# 1_Power_Supply.net
KiCad netlist of a schematic drawn in Altium Designer
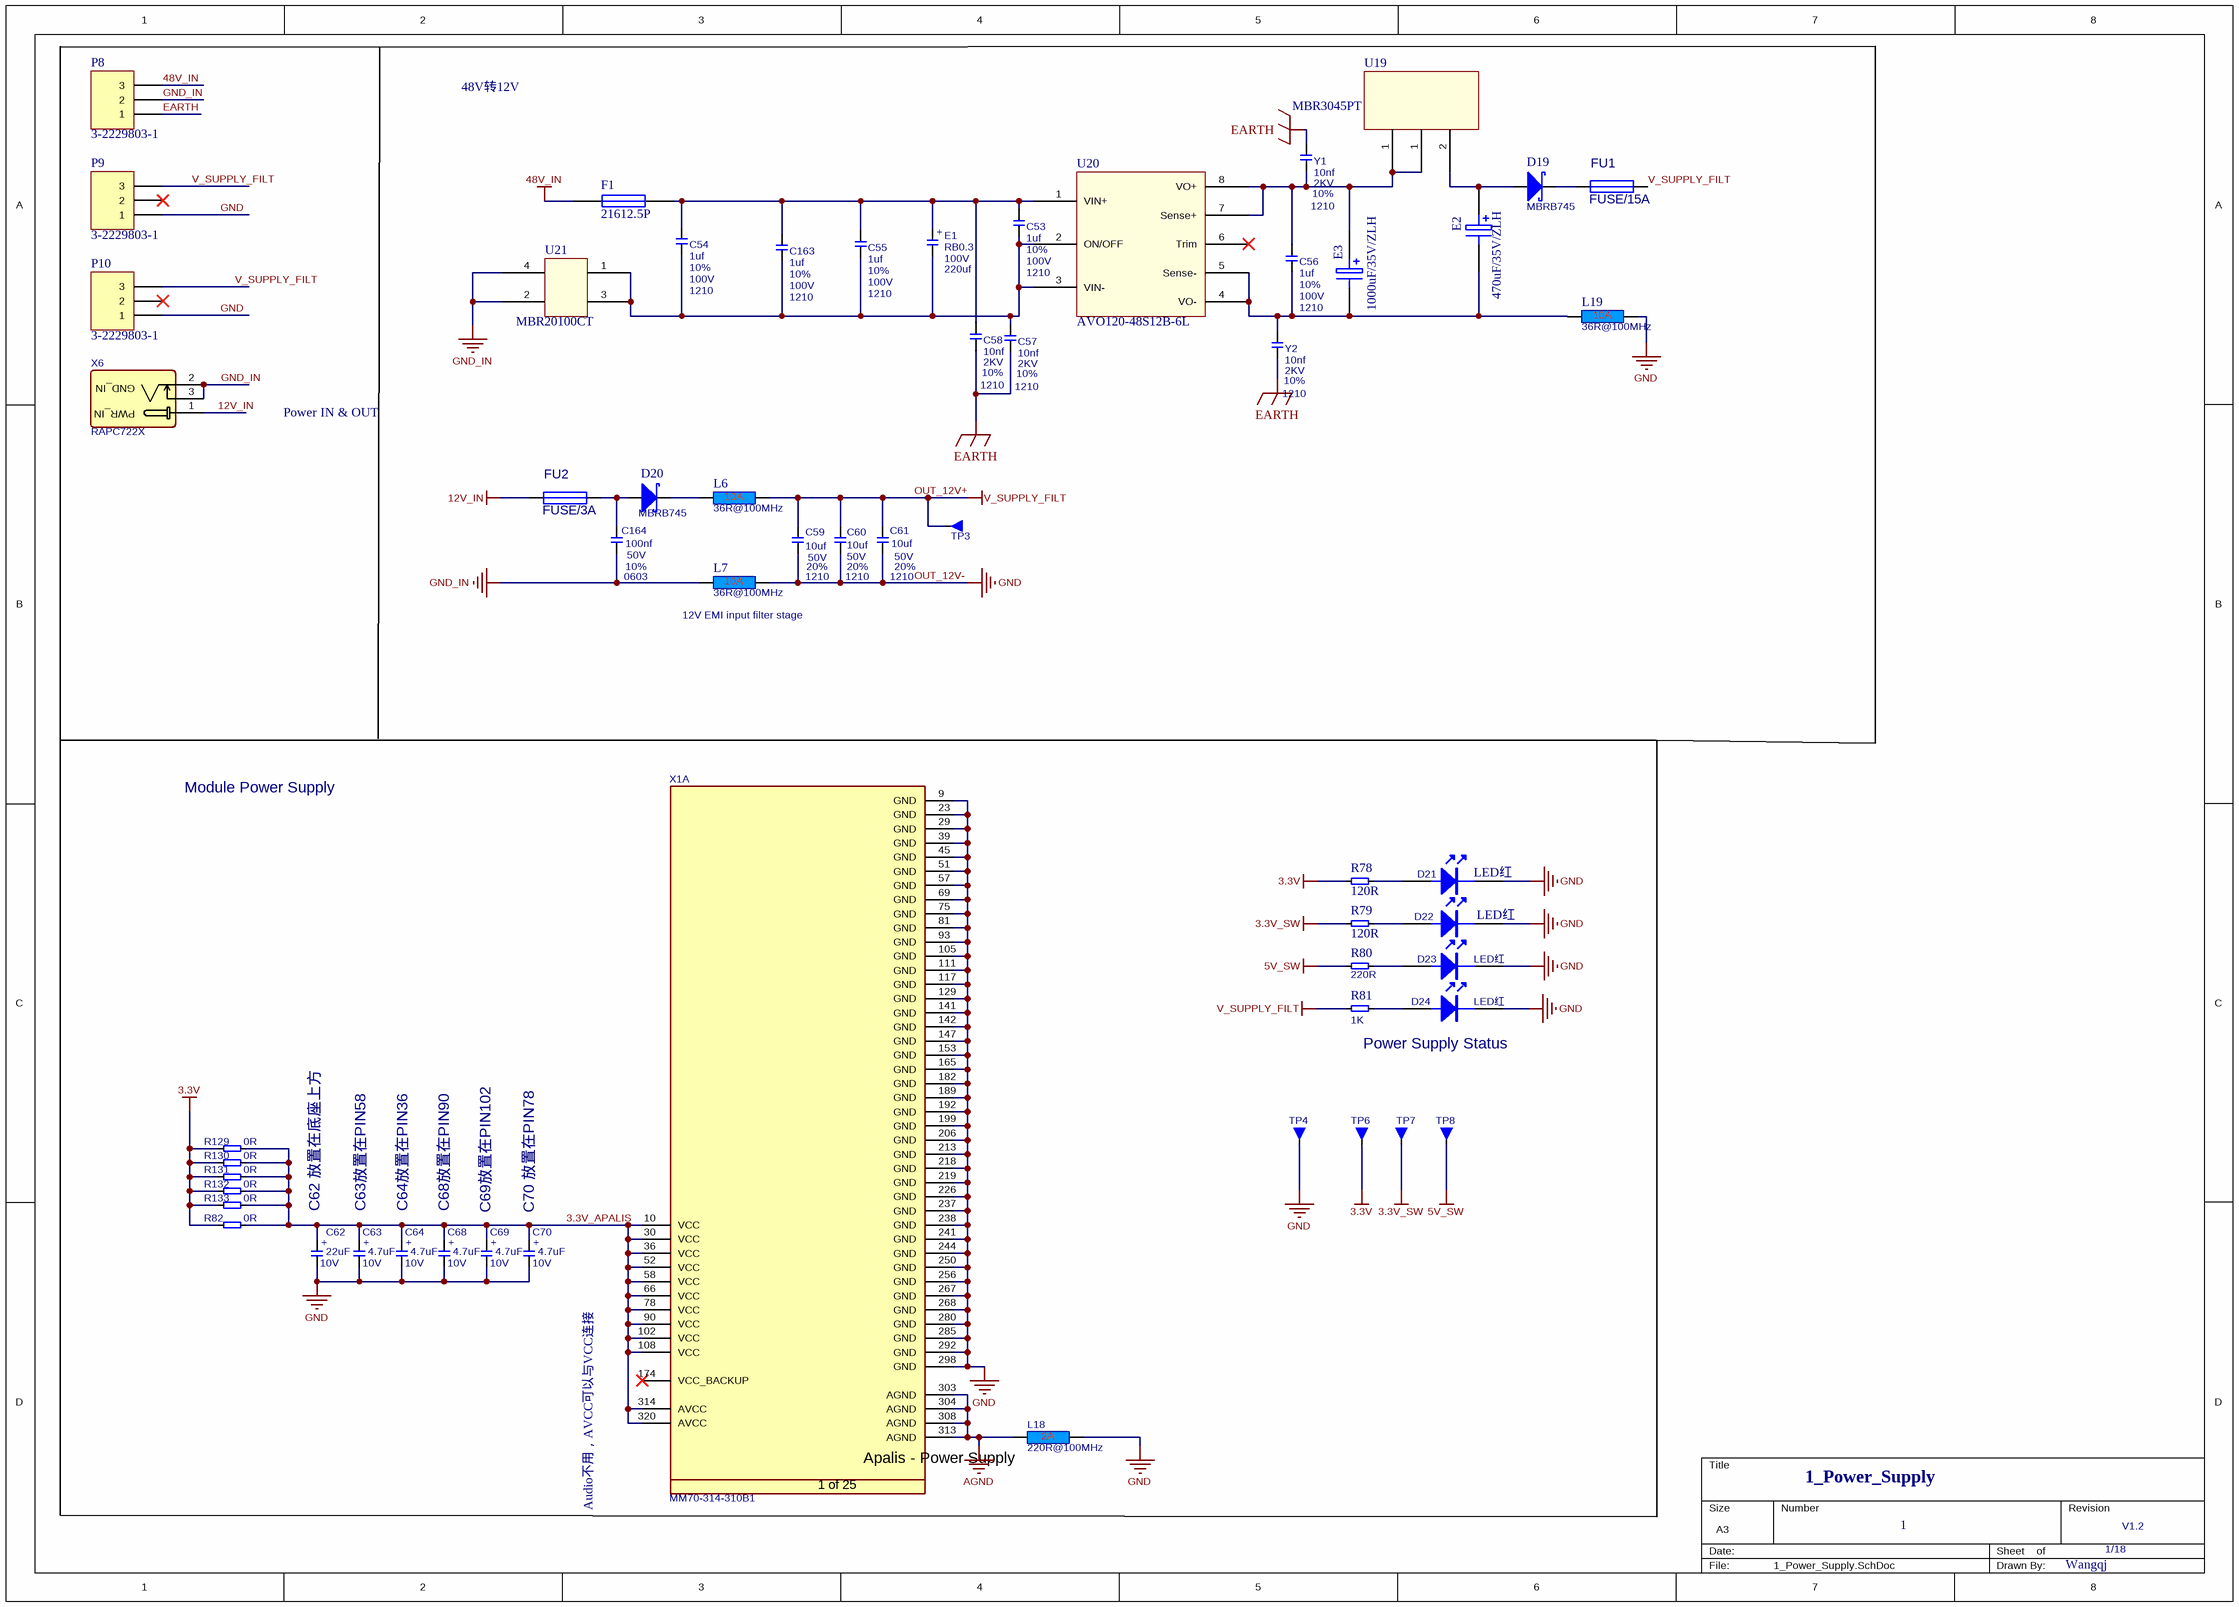
[diagram p0: 1_Power_Supply.SchDoc]

(export (version "E")
  (design (tool "Eeschema 10.0.6"))
  (components
    (comp (ref "C53")
      (value "1uf")
      (footprint "1210")
      (description "33pf-50V-5%-0603")
      (fields
        (field (name "TOLERANCE") "10%")
        (field (name "RATING") "100V")
        (field (name "Comment") "1uf-100V-10%-1210")
      )
      (libsource (lib "WangQJ") (part "C-Ceramic"))
    )
    (comp (ref "C54")
      (value "1uf")
      (footprint "1210")
      (description "33pf-50V-5%-0603")
      (fields
        (field (name "TOLERANCE") "10%")
        (field (name "RATING") "100V")
        (field (name "Comment") "1uf-100V-10%-1210")
      )
      (libsource (lib "WangQJ") (part "C-Ceramic"))
    )
    (comp (ref "C55")
      (value "1uf")
      (footprint "1210")
      (description "33pf-50V-5%-0603")
      (fields
        (field (name "TOLERANCE") "10%")
        (field (name "RATING") "100V")
        (field (name "Comment") "1uf-100V-10%-1210")
      )
      (libsource (lib "WangQJ") (part "C-Ceramic"))
    )
    (comp (ref "C56")
      (value "1uf")
      (footprint "1210")
      (description "33pf-50V-5%-0603")
      (fields
        (field (name "TOLERANCE") "10%")
        (field (name "RATING") "100V")
        (field (name "Comment") "1uf-100V-10%-1210")
      )
      (libsource (lib "WangQJ") (part "C-Ceramic"))
    )
    (comp (ref "C57")
      (value "10nf")
      (footprint "1210")
      (description "33pf-50V-5%-0603")
      (fields
        (field (name "TOLERANCE") "10%")
        (field (name "RATING") "2KV")
        (field (name "Comment") "10nf-2KV-10%-1210")
      )
      (libsource (lib "WangQJ") (part "C-Ceramic"))
    )
    (comp (ref "C58")
      (value "10nf")
      (footprint "1210")
      (description "33pf-50V-5%-0603")
      (fields
        (field (name "TOLERANCE") "10%")
        (field (name "RATING") "2KV")
        (field (name "Comment") "10nf-2KV-10%-1210")
      )
      (libsource (lib "WangQJ") (part "C-Ceramic"))
    )
    (comp (ref "C59")
      (value "10uf")
      (footprint "1210")
      (description "Capacitor Ceramic X5R 10uF 50V 20% 1210")
      (fields
        (field (name "TOLERANCE") "20%")
        (field (name "RATING") "50V")
        (field (name "Comment") "10uf-50V-20%-1210-X5R")
      )
      (libsource (lib "Apalis Evaluation Board") (part "C-10uF-50V-20%-1210-X5R"))
    )
    (comp (ref "C60")
      (value "10uf")
      (footprint "1210")
      (description "Capacitor Ceramic X5R 10uF 50V 20% 1210")
      (fields
        (field (name "TOLERANCE") "20%")
        (field (name "RATING") "50V")
        (field (name "Comment") "10uf-50V-20%-1210-X5R")
      )
      (libsource (lib "Apalis Evaluation Board") (part "C-10uF-50V-20%-1210-X5R"))
    )
    (comp (ref "C61")
      (value "10uf")
      (footprint "1210")
      (description "Capacitor Ceramic X5R 10uF 50V 20% 1210")
      (fields
        (field (name "TOLERANCE") "20%")
        (field (name "RATING") "50V")
        (field (name "Comment") "10uf-50V-20%-1210-X5R")
      )
      (libsource (lib "Apalis Evaluation Board") (part "C-10uF-50V-20%-1210-X5R"))
    )
    (comp (ref "C62")
      (value "22uF")
      (footprint "CAPMP3528X210N")
      (description "Capacitor TA 22uF 10V 20% 3528")
      (fields (field (name "TOLERANCE") "20%") (field (name "RATING") "10V"))
      (libsource (lib "Apalis Evaluation Board") (part "C-TA-22uF-10V-20%-3528"))
    )
    (comp (ref "C63")
      (value "4.7uF")
      (footprint "T_CAPMP3216X180N")
      (description "Capacitor TA 4.7uF 10V 20% 3216")
      (fields (field (name "TOLERANCE") "20%") (field (name "RATING") "10V"))
      (libsource (lib "Apalis Evaluation Board") (part "C-TA-4.7uF-10V-20%-3216"))
    )
    (comp (ref "C64")
      (value "4.7uF")
      (footprint "T_CAPMP3216X180N")
      (description "Capacitor TA 4.7uF 10V 20% 3216")
      (fields (field (name "TOLERANCE") "20%") (field (name "RATING") "10V"))
      (libsource (lib "Apalis Evaluation Board") (part "C-TA-4.7uF-10V-20%-3216"))
    )
    (comp (ref "C68")
      (value "4.7uF")
      (footprint "T_CAPMP3216X180N")
      (description "Capacitor TA 4.7uF 10V 20% 3216")
      (fields (field (name "TOLERANCE") "20%") (field (name "RATING") "10V"))
      (libsource (lib "Apalis Evaluation Board") (part "C-TA-4.7uF-10V-20%-3216"))
    )
    (comp (ref "C69")
      (value "4.7uF")
      (footprint "T_CAPMP3216X180N")
      (description "Capacitor TA 4.7uF 10V 20% 3216")
      (fields (field (name "TOLERANCE") "20%") (field (name "RATING") "10V"))
      (libsource (lib "Apalis Evaluation Board") (part "C-TA-4.7uF-10V-20%-3216"))
    )
    (comp (ref "C70")
      (value "4.7uF")
      (footprint "T_CAPMP3216X180N")
      (description "Capacitor TA 4.7uF 10V 20% 3216")
      (fields (field (name "TOLERANCE") "20%") (field (name "RATING") "10V"))
      (libsource (lib "Apalis Evaluation Board") (part "C-TA-4.7uF-10V-20%-3216"))
    )
    (comp (ref "C163")
      (value "1uf")
      (footprint "1210")
      (description "33pf-50V-5%-0603")
      (fields
        (field (name "TOLERANCE") "10%")
        (field (name "RATING") "100V")
        (field (name "Comment") "1uf-100V-10%-1210")
      )
      (libsource (lib "WangQJ") (part "C-Ceramic"))
    )
    (comp (ref "C164")
      (value "100nf")
      (footprint "0603")
      (description "Capacitor Ceramic X7R 100nF 50V 20% 0603")
      (fields
        (field (name "TOLERANCE") "10%")
        (field (name "RATING") "50V")
        (field (name "Comment") "100nf-50V-10%-0603-X7R")
      )
      (libsource (lib "Apalis Evaluation Board") (part "C-100nF-50V-20%-0603-X7R"))
    )
    (comp (ref "D19")
      (value "MBRB735PBF")
      (footprint "T_VISHAY_MBRB735PBF")
      (description "MBRB735PBF Schottky Diode")
      (fields (field (name "MANUFACTURER PART NO.") "MBRB745"))
      (libsource (lib "") (part "D-VISHAY-MBRB735PBF_1"))
    )
    (comp (ref "D20")
      (value "MBRB745")
      (footprint "T_VISHAY_MBRB735PBF")
      (description "MBRB735PBF Schottky Diode")
      (fields (field (name "MANUFACTURER PART NO.") "MBRB745"))
      (libsource (lib "Apalis Evaluation Board") (part "D-VISHAY-MBRB735PBF"))
    )
    (comp (ref "D21")
      (value "LED红")
      (footprint "LC-0805_LED_S3")
      (description "0805LED红")
      (libsource (lib "*") (part "LED"))
    )
    (comp (ref "D22")
      (value "LED红")
      (footprint "LC-0805_LED_S3")
      (description "0805LED红")
      (libsource (lib "*") (part "LED"))
    )
    (comp (ref "D23")
      (value "LED红")
      (footprint "LC-0805_LED_S3")
      (description "0805LED红")
      (libsource (lib "*") (part "LED"))
    )
    (comp (ref "D24")
      (value "LED红")
      (footprint "LC-0805_LED_S3")
      (description "0805LED红")
      (libsource (lib "*") (part "LED"))
    )
    (comp (ref "E1")
      (value "220uf")
      (footprint "RB0.3")
      (description "Capacitor TA")
      (fields
        (field (name "RATING") "100V")
        (field (name "TOLERANCE") "20%")
        (field (name "Comment") "220uf-100V-RB0.3")
      )
      (libsource (lib "WangQJ") (part "C-TA"))
    )
    (comp (ref "E2")
      (value "470uF/35V/ZLH")
      (footprint "RB0.3")
      (description "插装电解电容")
      (libsource (lib "*") (part "ELECTRO1"))
    )
    (comp (ref "E3")
      (value "1000uF/35V/ZLH")
      (footprint "5*13")
      (description "插装电解电容")
      (libsource (lib "*") (part "ELECTRO1"))
    )
    (comp (ref "F1")
      (value "21612.5P")
      (footprint "RAD0.3")
      (description "直插12.5A保险丝")
      (libsource (lib "*") (part "FUSE1"))
    )
    (comp (ref "FU1")
      (value "FUSE/15A")
      (footprint "FUSE-1808-3A")
      (description "贴片15A保险")
      (libsource (lib "常用元件库") (part "FUSE"))
    )
    (comp (ref "FU2")
      (value "FUSE/3A")
      (footprint "FUSE-1808-3A")
      (description "贴片3A保险")
      (libsource (lib "常用元件库") (part "FUSE"))
    )
    (comp (ref "L6")
      (value "36R@100MHz")
      (footprint "T_Laird_35F0121-0SR-10")
      (description "Power Supply FB 10A")
      (fields (field (name "TOLERANCE") "25%"))
      (libsource (lib "Apalis Evaluation Board") (part "L-Laird-35F0121-0SR-10-10A-25%"))
    )
    (comp (ref "L7")
      (value "36R@100MHz")
      (footprint "T_Laird_35F0121-0SR-10")
      (description "Power Supply FB 10A")
      (fields (field (name "TOLERANCE") "25%"))
      (libsource (lib "Apalis Evaluation Board") (part "L-Laird-35F0121-0SR-10-10A-25%"))
    )
    (comp (ref "L18")
      (value "220R@100MHz")
      (footprint "INDC1608X95N")
      (description "220R@100MHz 2A EMI FILTER")
      (fields (field (name "TOLERANCE") "25%"))
      (libsource (lib "Apalis Evaluation Board") (part "L-220R@100MHz-2A-25%-0603"))
    )
    (comp (ref "L19")
      (value "36R@100MHz")
      (footprint "T_Laird_35F0121-0SR-10")
      (description "Power Supply FB 10A")
      (fields (field (name "TOLERANCE") "25%"))
      (libsource (lib "Apalis Evaluation Board") (part "L-Laird-35F0121-0SR-10-10A-25%"))
    )
    (comp (ref "P8")
      (value "3-2229803-1")
      (footprint "3-2229803-1")
      (description "泰科电源端子座")
      (fields (field (name "PUBLISHER") "Altium Limited"))
      (libsource (lib "Miscellaneous Connectors") (part "Header 3"))
    )
    (comp (ref "P9")
      (value "3-2229803-1")
      (footprint "3-2229803-1")
      (description "泰科电源端子座")
      (fields (field (name "PUBLISHER") "Altium Limited"))
      (libsource (lib "Miscellaneous Connectors") (part "Header 3"))
    )
    (comp (ref "P10")
      (value "3-2229803-1")
      (footprint "3-2229803-1")
      (description "泰科电源端子座")
      (fields (field (name "PUBLISHER") "Altium Limited"))
      (libsource (lib "Miscellaneous Connectors") (part "Header 3"))
    )
    (comp (ref "R78")
      (value "120R")
      (footprint "T_RESC0603X30N")
      (description "Resistor 120 ohm 63mW 5% 0603")
      (fields (field (name "TOLERANCE") "5%"))
      (libsource (lib "Apalis Evaluation Board") (part "R-120R-63mW-5%-0603"))
    )
    (comp (ref "R79")
      (value "120R")
      (footprint "T_RESC0603X30N")
      (description "Resistor 120 ohm 63mW 5% 0603")
      (fields (field (name "TOLERANCE") "5%"))
      (libsource (lib "Apalis Evaluation Board") (part "R-120R-63mW-5%-0603"))
    )
    (comp (ref "R80")
      (value "220R")
      (footprint "T_RESC0603X30N")
      (description "Resistor 220 ohm 63mW 5% 0603")
      (fields (field (name "TOLERANCE") "5%"))
      (libsource (lib "Apalis Evaluation Board") (part "R-220R-63mW-5%-0603"))
    )
    (comp (ref "R81")
      (value "1K")
      (footprint "T_RESC0603X30N")
      (description "Resistor 1 Kohm 63mW 5% 0603")
      (fields (field (name "TOLERANCE") "5%"))
      (libsource (lib "Apalis Evaluation Board") (part "R-1KR-63mW-5%-0603"))
    )
    (comp (ref "R82")
      (value "0R")
      (footprint "T_RESC3216X760N")
      (description "Resistor 0 ohm 330mW 1% 1206")
      (fields (field (name "TOLERANCE") "1%"))
      (libsource (lib "Apalis Evaluation Board") (part "R-0R-63mW-1%-1206"))
    )
    (comp (ref "R129")
      (value "0R")
      (footprint "T_RESC3216X760N")
      (description "Resistor 0 ohm 63mW 1% 1206")
      (fields (field (name "TOLERANCE") "1%"))
      (libsource (lib "Apalis Evaluation Board") (part "R-0R-63mW-1%-1206"))
    )
    (comp (ref "R130")
      (value "0R")
      (footprint "T_RESC3216X760N")
      (description "Resistor 0 ohm 63mW 1% 1206")
      (fields (field (name "TOLERANCE") "1%"))
      (libsource (lib "Apalis Evaluation Board") (part "R-0R-63mW-1%-1206"))
    )
    (comp (ref "R131")
      (value "0R")
      (footprint "T_RESC3216X760N")
      (description "Resistor 0 ohm 63mW 1% 1206")
      (fields (field (name "TOLERANCE") "1%"))
      (libsource (lib "Apalis Evaluation Board") (part "R-0R-63mW-1%-1206"))
    )
    (comp (ref "R132")
      (value "0R")
      (footprint "T_RESC3216X760N")
      (description "Resistor 0 ohm 63mW 1% 1206")
      (fields (field (name "TOLERANCE") "1%"))
      (libsource (lib "Apalis Evaluation Board") (part "R-0R-63mW-1%-1206"))
    )
    (comp (ref "R133")
      (value "0R")
      (footprint "T_RESC3216X760N")
      (description "Resistor 0 ohm 63mW 1% 1206")
      (fields (field (name "TOLERANCE") "1%"))
      (libsource (lib "Apalis Evaluation Board") (part "R-0R-63mW-1%-1206"))
    )
    (comp (ref "TP3")
      (value "Testpin")
      (footprint "T_TP-THT")
      (description "Testpin TH")
      (libsource (lib "Apalis Evaluation Board") (part "Testpin"))
    )
    (comp (ref "TP4")
      (value "Testpin")
      (footprint "T_TP-THT")
      (description "Testpin TH")
      (libsource (lib "Apalis Evaluation Board") (part "Testpin"))
    )
    (comp (ref "TP6")
      (value "Testpin")
      (footprint "T_TP-THT")
      (description "Testpin TH")
      (libsource (lib "Apalis Evaluation Board") (part "Testpin"))
    )
    (comp (ref "TP7")
      (value "Testpin")
      (footprint "T_TP-THT")
      (description "Testpin TH")
      (libsource (lib "Apalis Evaluation Board") (part "Testpin"))
    )
    (comp (ref "TP8")
      (value "Testpin")
      (footprint "T_TP-THT")
      (description "Testpin TH")
      (libsource (lib "Apalis Evaluation Board") (part "Testpin"))
    )
    (comp (ref "U19")
      (value "MBR3045PT")
      (footprint "TO-3P")
      (description "插装肖特基二极管，加散热片")
      (libsource (lib "CCS14") (part "MBR3045T"))
    )
    (comp (ref "U20")
      (value "AVO120-48S12B-6L")
      (footprint "AVO120-48S12B-6L")
      (description "嵌入式48-12V电源模块")
      (libsource (lib "CCS14") (part "AVO120-48S12B-6L"))
    )
    (comp (ref "U21") (value "MBR20100CT") (footprint "TO-220") (libsource (lib "CCS14") (part "MBR20100CT")))
    (comp (ref "X1")
      (value "CON-JAE-MM70-314-310B1-314-0.5mm")
      (footprint "T_JAE_MM70-314-310B1")
      (description "MXM3 Connector")
      (fields (field (name "MANUFACTURER PART NO.") "MM70-314-310B1"))
      (libsource (lib "Apalis Evaluation Board") (part "CON-JAE-MM70-314-310B1-314-0.5mm"))
    )
    (comp (ref "X6")
      (value "RAPC722X")
      (footprint "DC-005")
      (description "Power Jack")
      (fields (field (name "MANUFACTURER PART NO.") "RAPC722X"))
      (libsource (lib "Apalis Evaluation Board") (part "CON-SWC-RAPC722X"))
    )
    (comp (ref "Y1")
      (value "10nf")
      (footprint "1210")
      (description "33pf-50V-5%-0603")
      (fields
        (field (name "TOLERANCE") "10%")
        (field (name "RATING") "2KV")
        (field (name "Comment") "10nf-2KV-10%-1210")
      )
      (libsource (lib "WangQJ") (part "C-Ceramic"))
    )
    (comp (ref "Y2")
      (value "10nf")
      (footprint "1210")
      (description "33pf-50V-5%-0603")
      (fields
        (field (name "TOLERANCE") "10%")
        (field (name "RATING") "2KV")
        (field (name "Comment") "10nf-2KV-10%-1210")
      )
      (libsource (lib "WangQJ") (part "C-Ceramic"))
    )
  )
  (nets
    (net (code "1") (name "/3.3V_APALIS") (class "Default")
      (node (ref "C62") (pin "1") (pinfunction "1_1") (pintype "passive"))
      (node (ref "C63") (pin "1") (pinfunction "1_1") (pintype "passive"))
      (node (ref "C64") (pin "1") (pinfunction "1_1") (pintype "passive"))
      (node (ref "C68") (pin "1") (pinfunction "1_1") (pintype "passive"))
      (node (ref "C69") (pin "1") (pinfunction "1_1") (pintype "passive"))
      (node (ref "C70") (pin "1") (pinfunction "1_1") (pintype "passive"))
      (node (ref "R129") (pin "2") (pinfunction "2_2") (pintype "passive"))
      (node (ref "R130") (pin "2") (pinfunction "2_2") (pintype "passive"))
      (node (ref "R131") (pin "2") (pinfunction "2_2") (pintype "passive"))
      (node (ref "R132") (pin "2") (pinfunction "2_2") (pintype "passive"))
      (node (ref "R133") (pin "2") (pinfunction "2_2") (pintype "passive"))
      (node (ref "R82") (pin "2") (pinfunction "2_2") (pintype "passive"))
      (node (ref "X1") (pin "10") (pinfunction "VCC_10") (pintype "passive"))
      (node (ref "X1") (pin "102") (pinfunction "VCC_102") (pintype "passive"))
      (node (ref "X1") (pin "108") (pinfunction "VCC_108") (pintype "passive"))
      (node (ref "X1") (pin "30") (pinfunction "VCC_30") (pintype "passive"))
      (node (ref "X1") (pin "314") (pinfunction "AVCC_314") (pintype "power_in"))
      (node (ref "X1") (pin "320") (pinfunction "AVCC_320") (pintype "passive"))
      (node (ref "X1") (pin "36") (pinfunction "VCC_36") (pintype "passive"))
      (node (ref "X1") (pin "52") (pinfunction "VCC_52") (pintype "passive"))
      (node (ref "X1") (pin "58") (pinfunction "VCC_58") (pintype "passive"))
      (node (ref "X1") (pin "66") (pinfunction "VCC_66") (pintype "passive"))
      (node (ref "X1") (pin "78") (pinfunction "VCC_78") (pintype "passive"))
      (node (ref "X1") (pin "90") (pinfunction "VCC_90") (pintype "passive"))
    )
    (net (code "2") (name "3.3V") (class "Default")
      (node (ref "R129") (pin "1") (pinfunction "1_1") (pintype "passive"))
      (node (ref "R130") (pin "1") (pinfunction "1_1") (pintype "passive"))
      (node (ref "R131") (pin "1") (pinfunction "1_1") (pintype "passive"))
      (node (ref "R132") (pin "1") (pinfunction "1_1") (pintype "passive"))
      (node (ref "R133") (pin "1") (pinfunction "1_1") (pintype "passive"))
      (node (ref "R78") (pin "1") (pinfunction "1_1") (pintype "passive"))
      (node (ref "R82") (pin "1") (pinfunction "1_1") (pintype "passive"))
      (node (ref "TP6") (pin "1") (pinfunction "1_1") (pintype "passive"))
    )
    (net (code "3") (name "3.3V_SW") (class "Default")
      (node (ref "R79") (pin "1") (pinfunction "1_1") (pintype "passive"))
      (node (ref "TP7") (pin "1") (pinfunction "1_1") (pintype "passive"))
    )
    (net (code "4") (name "5V_SW") (class "Default")
      (node (ref "R80") (pin "1") (pinfunction "1_1") (pintype "passive"))
      (node (ref "TP8") (pin "1") (pinfunction "1_1") (pintype "passive"))
    )
    (net (code "5") (name "12V_IN") (class "Default")
      (node (ref "FU2") (pin "1") (pinfunction "1_1") (pintype "passive"))
      (node (ref "X6") (pin "1") (pinfunction "GND_IN_1") (pintype "passive"))
    )
    (net (code "6") (name "48V_IN") (class "Default")
      (node (ref "F1") (pin "1") (pinfunction "1_1") (pintype "passive"))
      (node (ref "P8") (pin "3") (pinfunction "3_3") (pintype "passive"))
    )
    (net (code "7") (name "AGND") (class "Default")
      (node (ref "L18") (pin "1") (pinfunction "1_1") (pintype "passive"))
      (node (ref "X1") (pin "303") (pinfunction "AGND_303") (pintype "power_in"))
      (node (ref "X1") (pin "304") (pinfunction "AGND_304") (pintype "power_in"))
      (node (ref "X1") (pin "308") (pinfunction "AGND_308") (pintype "power_in"))
      (node (ref "X1") (pin "313") (pinfunction "AGND_313") (pintype "passive"))
    )
    (net (code "8") (name "EARTH") (class "Default")
      (node (ref "C57") (pin "1") (pinfunction "1_1") (pintype "passive"))
      (node (ref "C58") (pin "1") (pinfunction "1_1") (pintype "passive"))
      (node (ref "P8") (pin "1") (pinfunction "1_1") (pintype "passive"))
      (node (ref "Y1") (pin "2") (pinfunction "2_2") (pintype "passive"))
      (node (ref "Y2") (pin "1") (pinfunction "1_1") (pintype "passive"))
    )
    (net (code "9") (name "GND") (class "Default")
      (node (ref "C59") (pin "1") (pinfunction "1_1") (pintype "passive"))
      (node (ref "C60") (pin "1") (pinfunction "1_1") (pintype "passive"))
      (node (ref "C61") (pin "1") (pinfunction "1_1") (pintype "passive"))
      (node (ref "C62") (pin "2") (pinfunction "2_2") (pintype "passive"))
      (node (ref "C63") (pin "2") (pinfunction "2_2") (pintype "passive"))
      (node (ref "C64") (pin "2") (pinfunction "2_2") (pintype "passive"))
      (node (ref "C68") (pin "2") (pinfunction "2_2") (pintype "passive"))
      (node (ref "C69") (pin "2") (pinfunction "2_2") (pintype "passive"))
      (node (ref "C70") (pin "2") (pinfunction "2_2") (pintype "passive"))
      (node (ref "D21") (pin "K") (pinfunction "2_K") (pintype "passive"))
      (node (ref "D22") (pin "K") (pinfunction "2_K") (pintype "passive"))
      (node (ref "D23") (pin "K") (pinfunction "2_K") (pintype "passive"))
      (node (ref "D24") (pin "K") (pinfunction "2_K") (pintype "passive"))
      (node (ref "L18") (pin "2") (pinfunction "2_2") (pintype "passive"))
      (node (ref "L19") (pin "2") (pinfunction "2_2") (pintype "passive"))
      (node (ref "L7") (pin "2") (pinfunction "2_2") (pintype "passive"))
      (node (ref "P10") (pin "1") (pinfunction "1_1") (pintype "passive"))
      (node (ref "P9") (pin "1") (pinfunction "1_1") (pintype "passive"))
      (node (ref "TP4") (pin "1") (pinfunction "1_1") (pintype "passive"))
      (node (ref "X1") (pin "105") (pinfunction "GND_105") (pintype "power_in"))
      (node (ref "X1") (pin "111") (pinfunction "GND_111") (pintype "power_in"))
      (node (ref "X1") (pin "117") (pinfunction "GND_117") (pintype "power_in"))
      (node (ref "X1") (pin "129") (pinfunction "GND_129") (pintype "power_in"))
      (node (ref "X1") (pin "141") (pinfunction "GND_141") (pintype "power_in"))
      (node (ref "X1") (pin "142") (pinfunction "GND_142") (pintype "power_in"))
      (node (ref "X1") (pin "147") (pinfunction "GND_147") (pintype "power_in"))
      (node (ref "X1") (pin "153") (pinfunction "GND_153") (pintype "power_in"))
      (node (ref "X1") (pin "165") (pinfunction "GND_165") (pintype "power_in"))
      (node (ref "X1") (pin "182") (pinfunction "GND_182") (pintype "power_in"))
      (node (ref "X1") (pin "189") (pinfunction "GND_189") (pintype "power_in"))
      (node (ref "X1") (pin "192") (pinfunction "GND_192") (pintype "power_in"))
      (node (ref "X1") (pin "199") (pinfunction "GND_199") (pintype "power_in"))
      (node (ref "X1") (pin "206") (pinfunction "GND_206") (pintype "power_in"))
      (node (ref "X1") (pin "213") (pinfunction "GND_213") (pintype "power_in"))
      (node (ref "X1") (pin "218") (pinfunction "GND_218") (pintype "power_in"))
      (node (ref "X1") (pin "219") (pinfunction "GND_219") (pintype "power_in"))
      (node (ref "X1") (pin "226") (pinfunction "GND_226") (pintype "power_in"))
      (node (ref "X1") (pin "23") (pinfunction "GND_23") (pintype "passive"))
      (node (ref "X1") (pin "237") (pinfunction "GND_237") (pintype "power_in"))
      (node (ref "X1") (pin "238") (pinfunction "GND_238") (pintype "power_in"))
      (node (ref "X1") (pin "241") (pinfunction "GND_241") (pintype "power_in"))
      (node (ref "X1") (pin "244") (pinfunction "GND_244") (pintype "power_in"))
      (node (ref "X1") (pin "250") (pinfunction "GND_250") (pintype "power_in"))
      (node (ref "X1") (pin "256") (pinfunction "GND_256") (pintype "power_in"))
      (node (ref "X1") (pin "267") (pinfunction "GND_267") (pintype "power_in"))
      (node (ref "X1") (pin "268") (pinfunction "GND_268") (pintype "power_in"))
      (node (ref "X1") (pin "280") (pinfunction "GND_280") (pintype "power_in"))
      (node (ref "X1") (pin "285") (pinfunction "GND_285") (pintype "power_in"))
      (node (ref "X1") (pin "29") (pinfunction "GND_29") (pintype "power_in"))
      (node (ref "X1") (pin "292") (pinfunction "GND_292") (pintype "power_in"))
      (node (ref "X1") (pin "298") (pinfunction "GND_298") (pintype "power_in"))
      (node (ref "X1") (pin "39") (pinfunction "GND_39") (pintype "power_in"))
      (node (ref "X1") (pin "45") (pinfunction "GND_45") (pintype "power_in"))
      (node (ref "X1") (pin "51") (pinfunction "GND_51") (pintype "power_in"))
      (node (ref "X1") (pin "57") (pinfunction "GND_57") (pintype "power_in"))
      (node (ref "X1") (pin "69") (pinfunction "GND_69") (pintype "power_in"))
      (node (ref "X1") (pin "75") (pinfunction "GND_75") (pintype "power_in"))
      (node (ref "X1") (pin "81") (pinfunction "GND_81") (pintype "power_in"))
      (node (ref "X1") (pin "9") (pinfunction "GND_9") (pintype "passive"))
      (node (ref "X1") (pin "93") (pinfunction "GND_93") (pintype "power_in"))
    )
    (net (code "10") (name "GND_IN") (class "Default")
      (node (ref "C164") (pin "1") (pinfunction "1_1") (pintype "passive"))
      (node (ref "L7") (pin "1") (pinfunction "1_1") (pintype "passive"))
      (node (ref "P8") (pin "2") (pinfunction "2_2") (pintype "passive"))
      (node (ref "U21") (pin "2") (pintype "passive"))
      (node (ref "U21") (pin "4") (pintype "passive"))
      (node (ref "X6") (pin "2") (pinfunction "PWR_IN_2") (pintype "passive"))
      (node (ref "X6") (pin "3") (pinfunction "PWR_IN_3") (pintype "passive"))
    )
    (net (code "11") (name "Net-(C164-Pad2)") (class "Default")
      (node (ref "C164") (pin "2") (pinfunction "2_2") (pintype "passive"))
      (node (ref "D20") (pin "3") (pinfunction "3_3") (pintype "passive"))
      (node (ref "FU2") (pin "2") (pinfunction "2_2") (pintype "passive"))
    )
    (net (code "12") (name "Net-(D19-Pad2)") (class "Default")
      (node (ref "D19") (pin "2") (pinfunction "2_2") (pintype "passive"))
      (node (ref "FU1") (pin "1") (pinfunction "1_1") (pintype "passive"))
    )
    (net (code "13") (name "Net-(D19-Pad3)") (class "Default")
      (node (ref "D19") (pin "3") (pinfunction "3_3") (pintype "passive"))
      (node (ref "E2") (pin "1") (pinfunction "1_1") (pintype "passive"))
      (node (ref "U19") (pin "2") (pintype "passive"))
    )
    (net (code "14") (name "Net-(D20-Pad2)") (class "Default")
      (node (ref "D20") (pin "2") (pinfunction "2_2") (pintype "passive"))
      (node (ref "L6") (pin "1") (pinfunction "1_1") (pintype "passive"))
    )
    (net (code "15") (name "Net-(D21-1)") (class "Default")
      (node (ref "D21") (pin "A") (pinfunction "1_A") (pintype "passive"))
      (node (ref "R78") (pin "2") (pinfunction "2_2") (pintype "passive"))
    )
    (net (code "16") (name "Net-(D22-1)") (class "Default")
      (node (ref "D22") (pin "A") (pinfunction "1_A") (pintype "passive"))
      (node (ref "R79") (pin "2") (pinfunction "2_2") (pintype "passive"))
    )
    (net (code "17") (name "Net-(D23-1)") (class "Default")
      (node (ref "D23") (pin "A") (pinfunction "1_A") (pintype "passive"))
      (node (ref "R80") (pin "2") (pinfunction "2_2") (pintype "passive"))
    )
    (net (code "18") (name "Net-(D24-1)") (class "Default")
      (node (ref "D24") (pin "A") (pinfunction "1_A") (pintype "passive"))
      (node (ref "R81") (pin "2") (pinfunction "2_2") (pintype "passive"))
    )
    (net (code "19") (name "Net-(U20-ON{slash}OFF)") (class "Default")
      (node (ref "C163") (pin "1") (pinfunction "1_1") (pintype "passive"))
      (node (ref "C53") (pin "1") (pinfunction "1_1") (pintype "passive"))
      (node (ref "C54") (pin "1") (pinfunction "1_1") (pintype "passive"))
      (node (ref "C55") (pin "1") (pinfunction "1_1") (pintype "passive"))
      (node (ref "C57") (pin "2") (pinfunction "2_2") (pintype "passive"))
      (node (ref "E1") (pin "2") (pinfunction "2_2") (pintype "passive"))
      (node (ref "U20") (pin "2") (pinfunction "ON/OFF_2") (pintype "passive"))
      (node (ref "U20") (pin "3") (pinfunction "VIN-_3") (pintype "passive"))
      (node (ref "U21") (pin "1") (pintype "passive"))
      (node (ref "U21") (pin "3") (pintype "passive"))
    )
    (net (code "20") (name "Net-(U20-Sense+)") (class "Default")
      (node (ref "C56") (pin "2") (pinfunction "2_2") (pintype "passive"))
      (node (ref "E3") (pin "1") (pinfunction "1_1") (pintype "passive"))
      (node (ref "U19") (pin "1") (pintype "passive"))
      (node (ref "U20") (pin "7") (pinfunction "Sense+_7") (pintype "passive"))
      (node (ref "U20") (pin "8") (pinfunction "VO+_8") (pintype "passive"))
      (node (ref "Y1") (pin "1") (pinfunction "1_1") (pintype "passive"))
    )
    (net (code "21") (name "Net-(U20-Sense-)") (class "Default")
      (node (ref "C56") (pin "1") (pinfunction "1_1") (pintype "passive"))
      (node (ref "E2") (pin "2") (pinfunction "2_2") (pintype "passive"))
      (node (ref "E3") (pin "2") (pinfunction "2_2") (pintype "passive"))
      (node (ref "L19") (pin "1") (pinfunction "1_1") (pintype "passive"))
      (node (ref "U20") (pin "4") (pinfunction "VO-_4") (pintype "passive"))
      (node (ref "U20") (pin "5") (pinfunction "Sense-_5") (pintype "passive"))
      (node (ref "Y2") (pin "2") (pinfunction "2_2") (pintype "passive"))
    )
    (net (code "22") (name "Net-(U20-VIN+)") (class "Default")
      (node (ref "C163") (pin "2") (pinfunction "2_2") (pintype "passive"))
      (node (ref "C53") (pin "2") (pinfunction "2_2") (pintype "passive"))
      (node (ref "C54") (pin "2") (pinfunction "2_2") (pintype "passive"))
      (node (ref "C55") (pin "2") (pinfunction "2_2") (pintype "passive"))
      (node (ref "C58") (pin "2") (pinfunction "2_2") (pintype "passive"))
      (node (ref "E1") (pin "1") (pinfunction "1_1") (pintype "passive"))
      (node (ref "F1") (pin "2") (pinfunction "2_2") (pintype "passive"))
      (node (ref "U20") (pin "1") (pinfunction "VIN+_1") (pintype "passive"))
    )
    (net (code "23") (name "V_SUPPLY_FILT") (class "Default")
      (node (ref "C59") (pin "2") (pinfunction "2_2") (pintype "passive"))
      (node (ref "C60") (pin "2") (pinfunction "2_2") (pintype "passive"))
      (node (ref "C61") (pin "2") (pinfunction "2_2") (pintype "passive"))
      (node (ref "FU1") (pin "2") (pinfunction "2_2") (pintype "passive"))
      (node (ref "L6") (pin "2") (pinfunction "2_2") (pintype "passive"))
      (node (ref "P10") (pin "3") (pinfunction "3_3") (pintype "passive"))
      (node (ref "P9") (pin "3") (pinfunction "3_3") (pintype "passive"))
      (node (ref "R81") (pin "1") (pinfunction "1_1") (pintype "passive"))
      (node (ref "TP3") (pin "1") (pinfunction "1_1") (pintype "passive"))
    )
    (net (code "24") (name "unconnected-(P9-Pad2)") (class "Default")
      (node (ref "P9") (pin "2") (pinfunction "2_2") (pintype "passive+no_connect"))
    )
    (net (code "25") (name "unconnected-(P10-Pad2)") (class "Default")
      (node (ref "P10") (pin "2") (pinfunction "2_2") (pintype "passive+no_connect"))
    )
    (net (code "26") (name "unconnected-(U20-Trim-Pad6)") (class "Default")
      (node (ref "U20") (pin "6") (pinfunction "Trim_6") (pintype "passive+no_connect"))
    )
    (net (code "27") (name "unconnected-(X1A-VCC_BACKUP-Pad174)") (class "Default")
      (node (ref "X1") (pin "174") (pinfunction "VCC_BACKUP_174") (pintype "passive+no_connect"))
    )
  )
)
